# Arduino-DUE-V03-Rocket.net
KiCad netlist of a schematic drawn in EAGLE
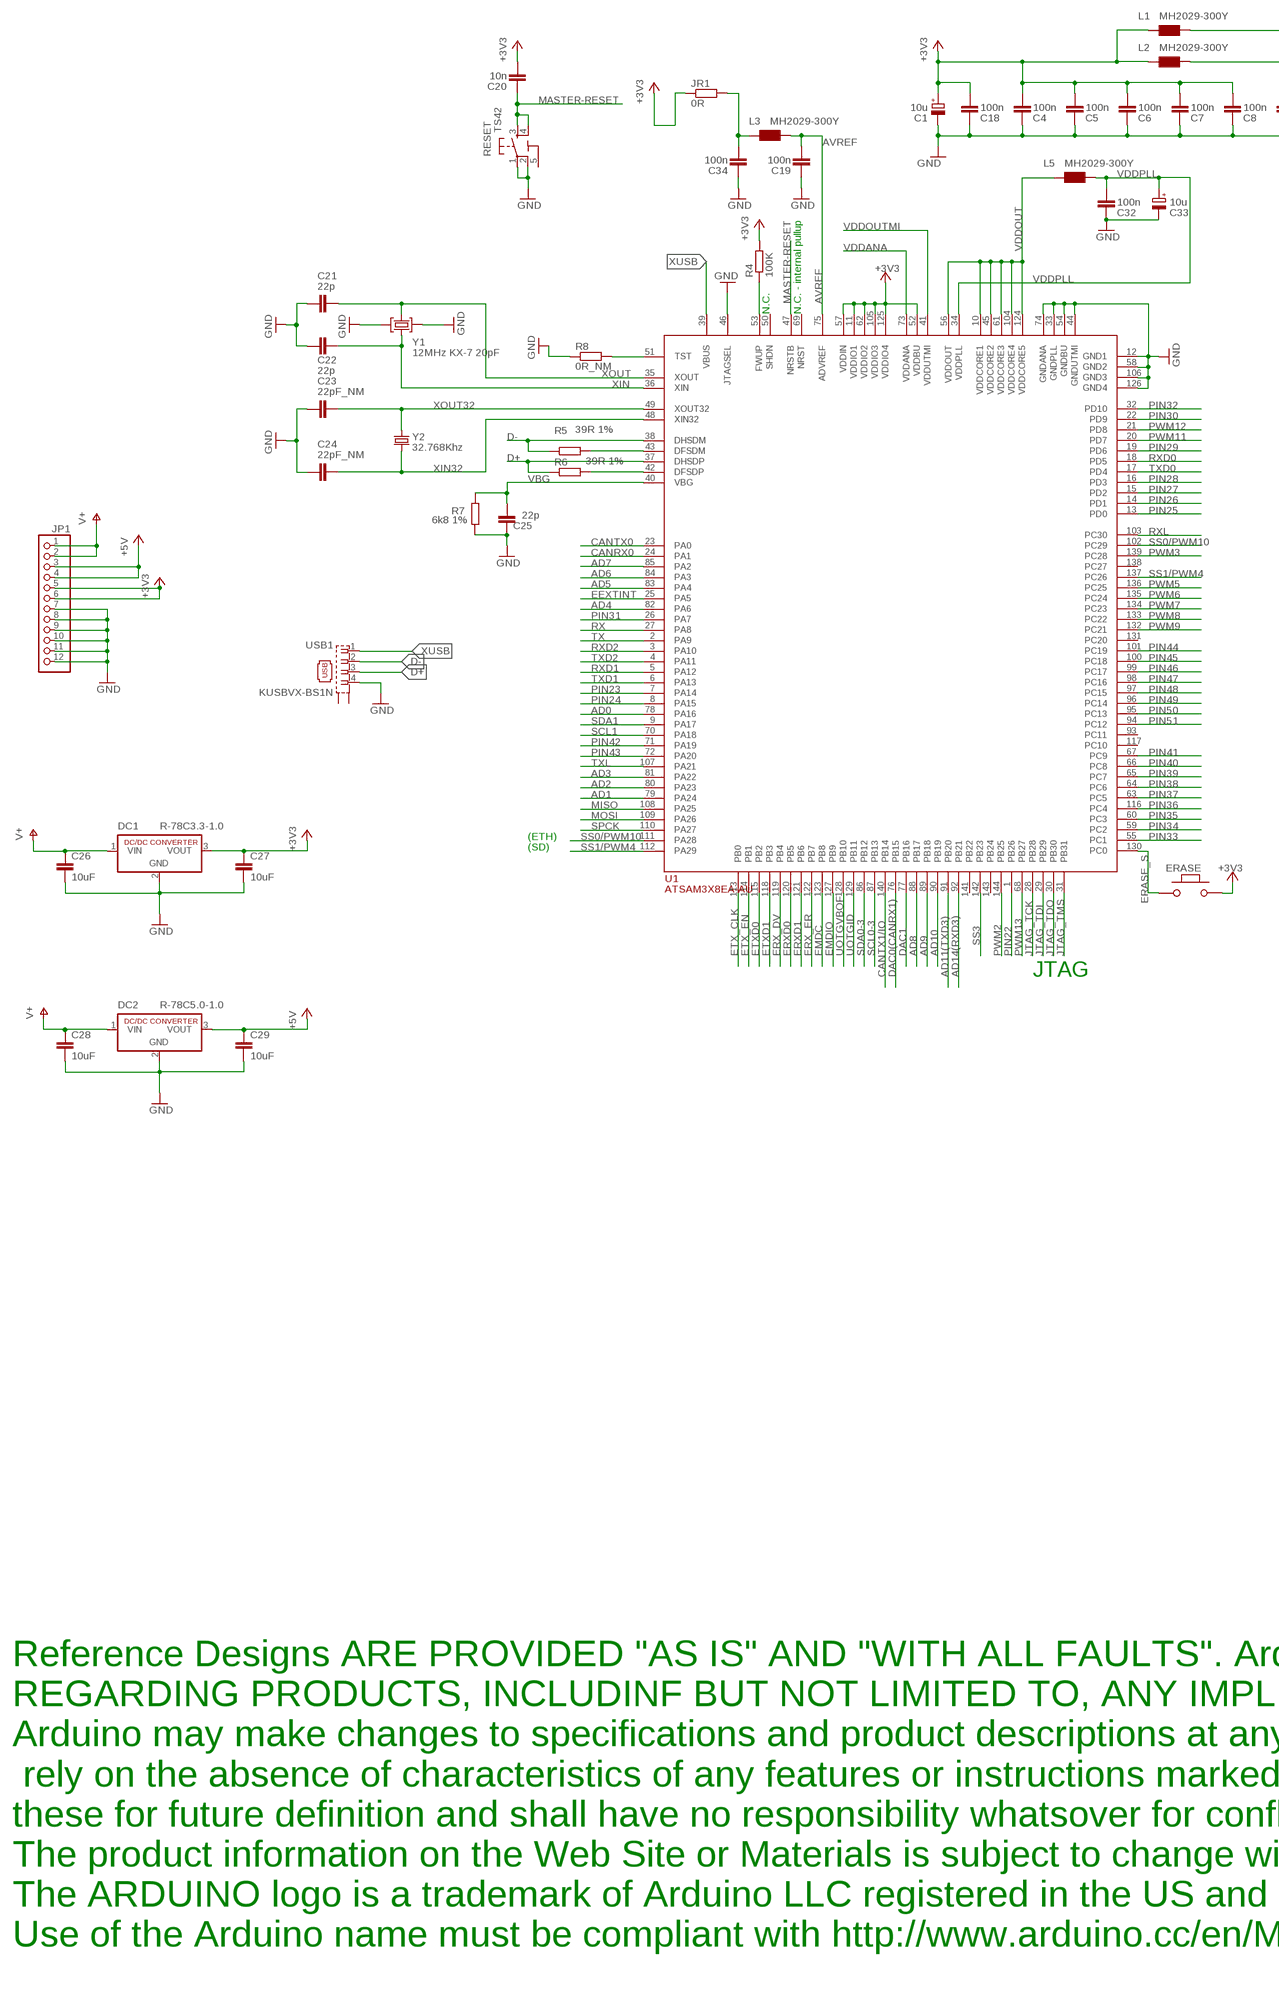
[diagram p0: schematic, sheet 1, part 1 of 2]
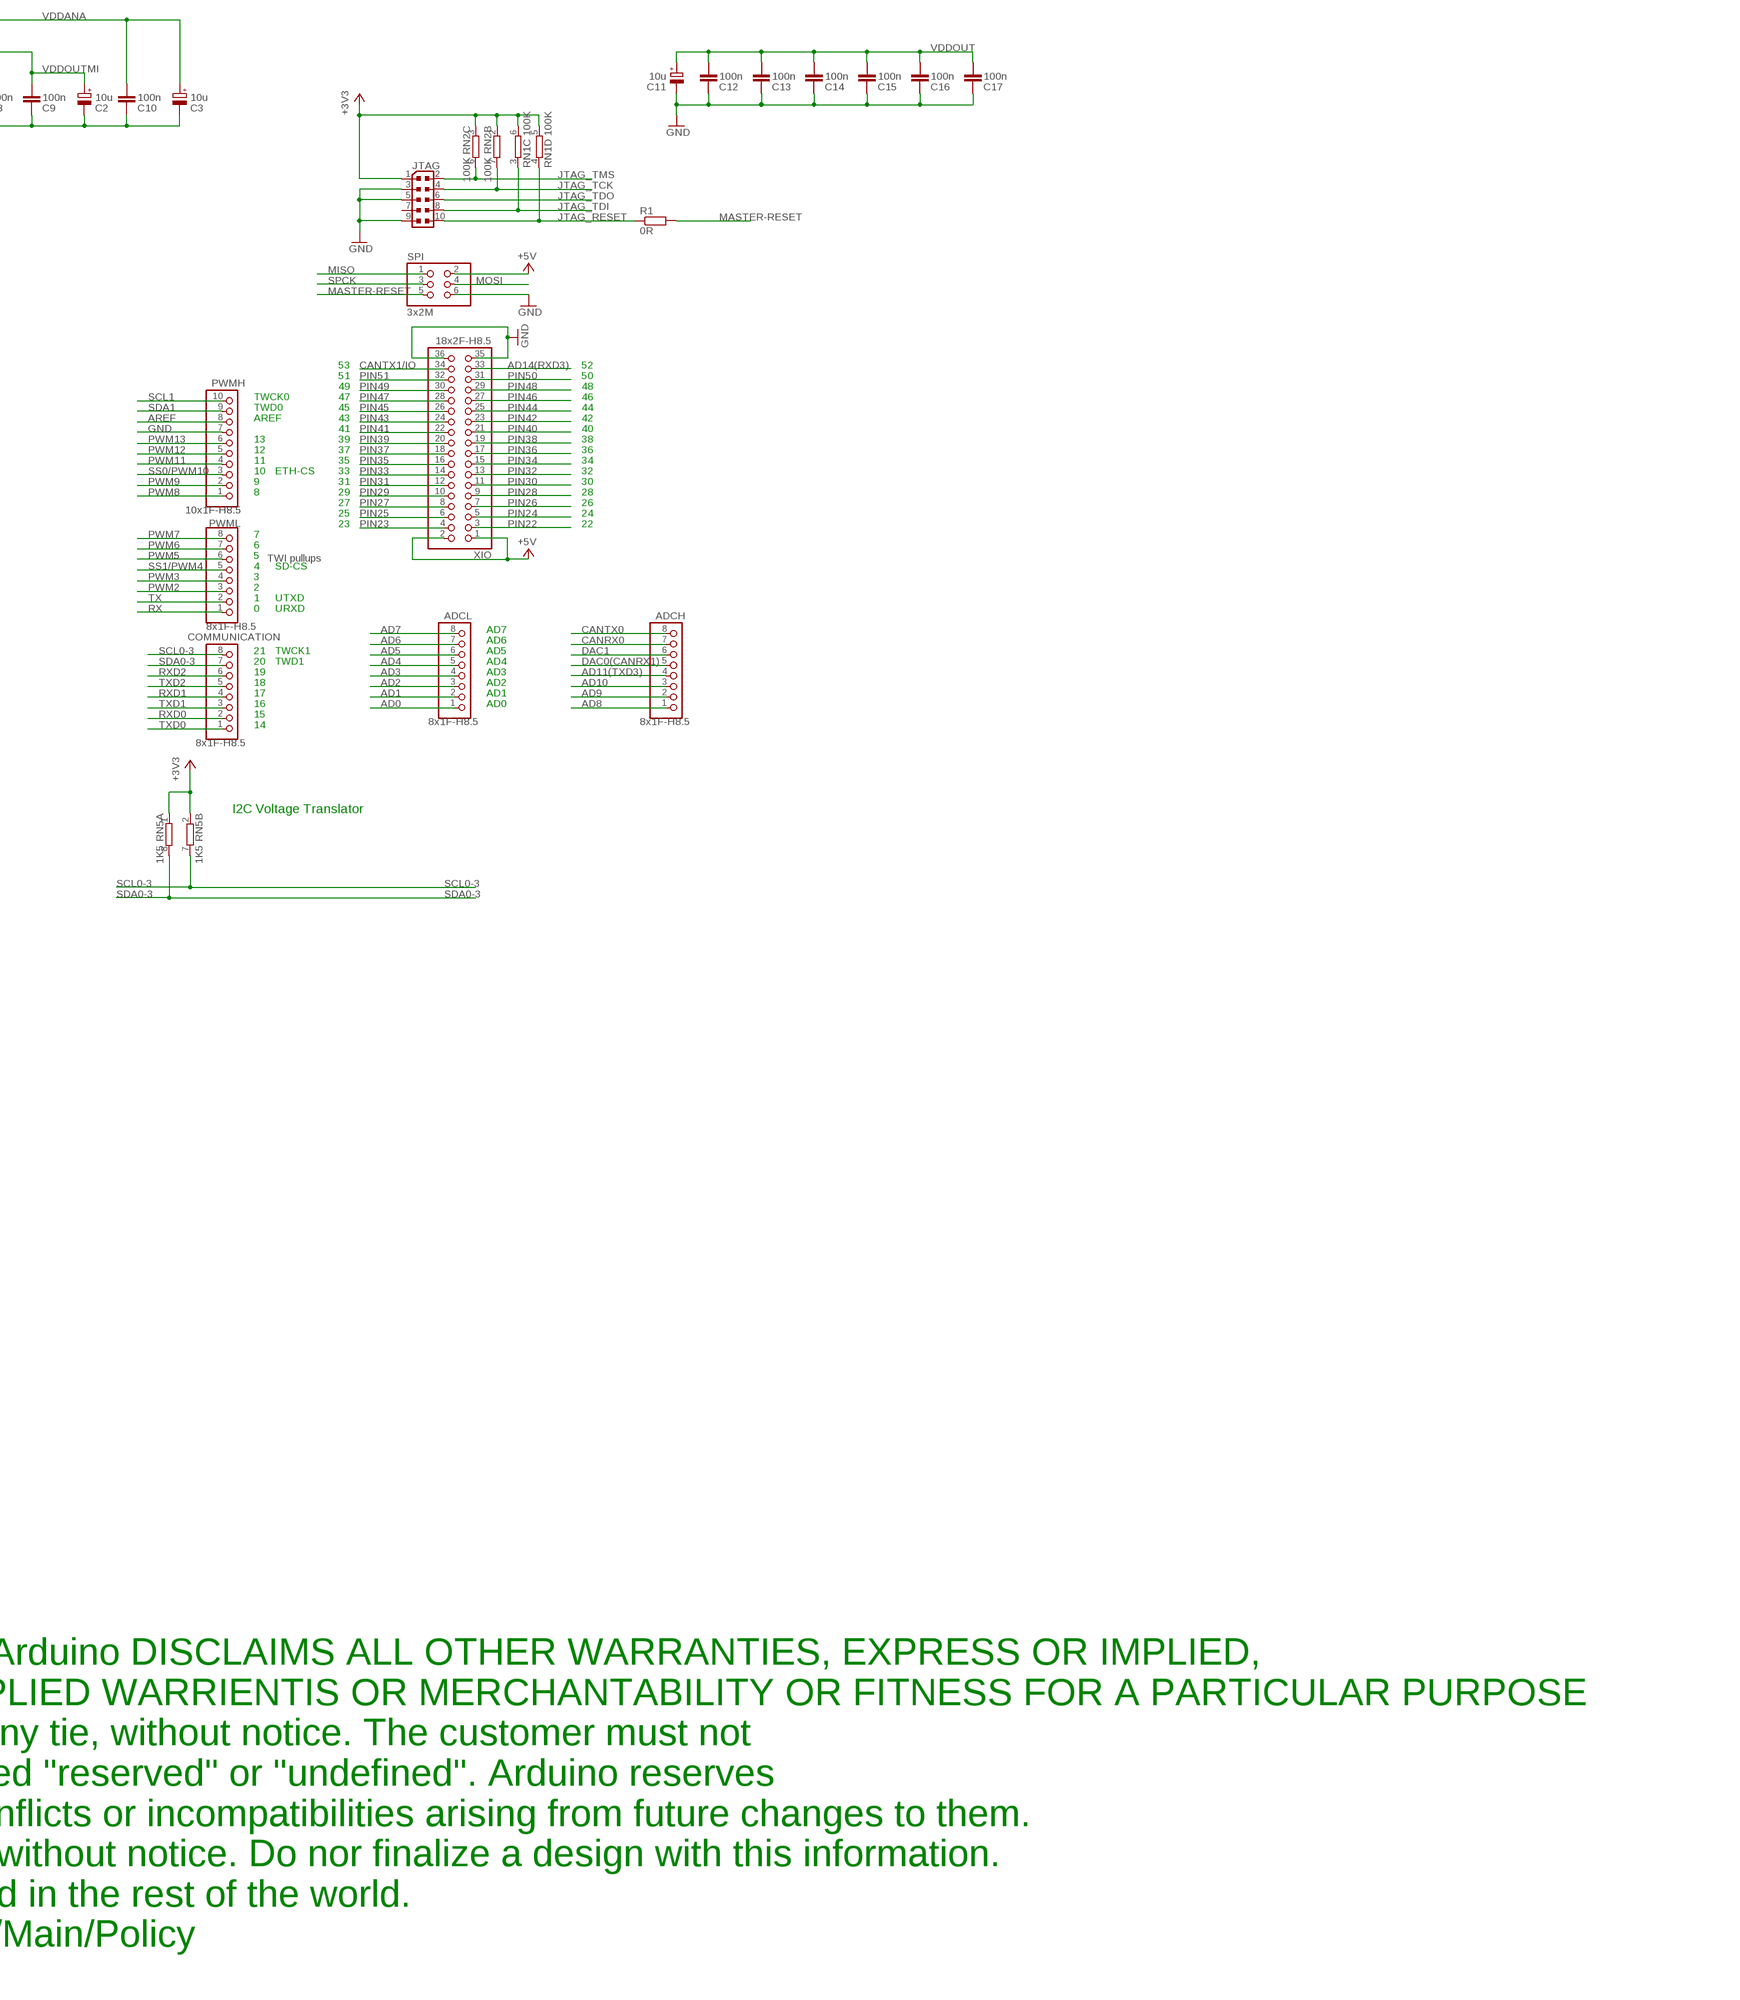
[diagram p1: schematic, sheet 1, part 2 of 2]

(export (version "E")
  (design (tool "Eeschema 10.0.6"))
  (components
    (comp (ref "ADCH")
      (value "8x1F-H8.5")
      (footprint "eagle-import:1X08")
      (libsource (lib "eagle-import") (part "PINHD-1X8"))
    )
    (comp (ref "ADCL")
      (value "8x1F-H8.5")
      (footprint "eagle-import:1X08")
      (libsource (lib "eagle-import") (part "PINHD-1X8"))
    )
    (comp (ref "C1")
      (value "10u")
      (footprint "eagle-import:SMC_B")
      (libsource (lib "eagle-import") (part "CPOL-EUSMCB"))
    )
    (comp (ref "C2")
      (value "10u")
      (footprint "eagle-import:SMC_B")
      (libsource (lib "eagle-import") (part "CPOL-EUSMCB"))
    )
    (comp (ref "C3")
      (value "10u")
      (footprint "eagle-import:SMC_B")
      (libsource (lib "eagle-import") (part "CPOL-EUSMCB"))
    )
    (comp (ref "C4")
      (value "100n")
      (footprint "eagle-import:C0402")
      (libsource (lib "eagle-import") (part "C-EUC0402"))
    )
    (comp (ref "C5")
      (value "100n")
      (footprint "eagle-import:C0402")
      (libsource (lib "eagle-import") (part "C-EUC0402"))
    )
    (comp (ref "C6")
      (value "100n")
      (footprint "eagle-import:C0402")
      (libsource (lib "eagle-import") (part "C-EUC0402"))
    )
    (comp (ref "C7")
      (value "100n")
      (footprint "eagle-import:C0402")
      (libsource (lib "eagle-import") (part "C-EUC0402"))
    )
    (comp (ref "C8")
      (value "100n")
      (footprint "eagle-import:C0402")
      (libsource (lib "eagle-import") (part "C-EUC0402"))
    )
    (comp (ref "C9")
      (value "100n")
      (footprint "eagle-import:C0402")
      (libsource (lib "eagle-import") (part "C-EUC0402"))
    )
    (comp (ref "C10")
      (value "100n")
      (footprint "eagle-import:C0402")
      (libsource (lib "eagle-import") (part "C-EUC0402"))
    )
    (comp (ref "C11")
      (value "10u")
      (footprint "eagle-import:SMC_B")
      (libsource (lib "eagle-import") (part "CPOL-EUSMCB"))
    )
    (comp (ref "C12")
      (value "100n")
      (footprint "eagle-import:C0402")
      (libsource (lib "eagle-import") (part "C-EUC0402"))
    )
    (comp (ref "C13")
      (value "100n")
      (footprint "eagle-import:C0402")
      (libsource (lib "eagle-import") (part "C-EUC0402"))
    )
    (comp (ref "C14")
      (value "100n")
      (footprint "eagle-import:C0402")
      (libsource (lib "eagle-import") (part "C-EUC0402"))
    )
    (comp (ref "C15")
      (value "100n")
      (footprint "eagle-import:C0402")
      (libsource (lib "eagle-import") (part "C-EUC0402"))
    )
    (comp (ref "C16")
      (value "100n")
      (footprint "eagle-import:C0402")
      (libsource (lib "eagle-import") (part "C-EUC0402"))
    )
    (comp (ref "C17")
      (value "100n")
      (footprint "eagle-import:C0402")
      (libsource (lib "eagle-import") (part "C-EUC0402"))
    )
    (comp (ref "C18")
      (value "100n")
      (footprint "eagle-import:C0402")
      (libsource (lib "eagle-import") (part "C-EUC0402"))
    )
    (comp (ref "C19")
      (value "100n")
      (footprint "eagle-import:C0402")
      (libsource (lib "eagle-import") (part "C-EUC0402"))
    )
    (comp (ref "C20")
      (value "10n")
      (footprint "eagle-import:C0402")
      (libsource (lib "eagle-import") (part "C-EUC0402"))
    )
    (comp (ref "C21")
      (value "22p")
      (footprint "eagle-import:C0402")
      (libsource (lib "eagle-import") (part "C-EUC0402"))
    )
    (comp (ref "C22")
      (value "22p")
      (footprint "eagle-import:C0402")
      (libsource (lib "eagle-import") (part "C-EUC0402"))
    )
    (comp (ref "C23")
      (value "22pF_NM")
      (footprint "eagle-import:C0402")
      (libsource (lib "eagle-import") (part "C-EUC0402"))
    )
    (comp (ref "C24")
      (value "22pF_NM")
      (footprint "eagle-import:C0402")
      (libsource (lib "eagle-import") (part "C-EUC0402"))
    )
    (comp (ref "C25")
      (value "22p")
      (footprint "eagle-import:C0402")
      (libsource (lib "eagle-import") (part "C-EUC0402"))
    )
    (comp (ref "C26")
      (value "10uF")
      (footprint "eagle-import:C050-030X075")
      (libsource (lib "eagle-import") (part "resistor_348_C-EU050-030X075"))
    )
    (comp (ref "C27")
      (value "10uF")
      (footprint "eagle-import:C050-030X075")
      (libsource (lib "eagle-import") (part "resistor_348_C-EU050-030X075"))
    )
    (comp (ref "C28")
      (value "10uF")
      (footprint "eagle-import:C050-030X075")
      (libsource (lib "eagle-import") (part "resistor_348_C-EU050-030X075"))
    )
    (comp (ref "C29")
      (value "10uF")
      (footprint "eagle-import:C050-030X075")
      (libsource (lib "eagle-import") (part "resistor_348_C-EU050-030X075"))
    )
    (comp (ref "C32")
      (value "100n")
      (footprint "eagle-import:C0402")
      (libsource (lib "eagle-import") (part "C-EUC0402"))
    )
    (comp (ref "C33")
      (value "10u")
      (footprint "eagle-import:SMC_B")
      (libsource (lib "eagle-import") (part "CPOL-EUSMCB"))
    )
    (comp (ref "C34")
      (value "100n")
      (footprint "eagle-import:C0402")
      (libsource (lib "eagle-import") (part "C-EUC0402"))
    )
    (comp (ref "COMMUNICATION")
      (value "8x1F-H8.5")
      (footprint "eagle-import:1X08")
      (libsource (lib "eagle-import") (part "PINHD-1X8"))
    )
    (comp (ref "DC1")
      (value "R-78C3.3-1.0")
      (footprint "eagle-import:SIP3")
      (libsource (lib "eagle-import") (part "R-78C-1.03.3"))
    )
    (comp (ref "DC2")
      (value "R-78C5.0-1.0")
      (footprint "eagle-import:SIP3")
      (libsource (lib "eagle-import") (part "R-78C-1.05.0"))
    )
    (comp (ref "ERASE")
      (value "MYSMD_PB157")
      (footprint "eagle-import:SMD_157SW")
      (libsource (lib "eagle-import") (part "MYSMD_PB157"))
    )
    (comp (ref "JP1")
      (value "PINHD-1X12")
      (footprint "eagle-import:1X12")
      (libsource (lib "eagle-import") (part "PINHD-1X12"))
    )
    (comp (ref "JR1")
      (value "0R")
      (footprint "eagle-import:R0402")
      (libsource (lib "eagle-import") (part "R-EU_R0402"))
    )
    (comp (ref "JTAG")
      (value "PINHEAD_PINHD-2X5PASSO127")
      (footprint "eagle-import:PINHEAD_2X05_127")
      (libsource (lib "eagle-import") (part "PINHEAD_PINHD-2X5PASSO127"))
    )
    (comp (ref "L1")
      (value "MH2029-300Y")
      (footprint "eagle-import:0805")
      (libsource (lib "eagle-import") (part "WE-CBF_0805"))
    )
    (comp (ref "L2")
      (value "MH2029-300Y")
      (footprint "eagle-import:0805")
      (libsource (lib "eagle-import") (part "WE-CBF_0805"))
    )
    (comp (ref "L3")
      (value "MH2029-300Y")
      (footprint "eagle-import:0805")
      (libsource (lib "eagle-import") (part "WE-CBF_0805"))
    )
    (comp (ref "L5")
      (value "MH2029-300Y")
      (footprint "eagle-import:0805")
      (libsource (lib "eagle-import") (part "WE-CBF_0805"))
    )
    (comp (ref "PWMH")
      (value "10x1F-H8.5")
      (footprint "eagle-import:1X10")
      (libsource (lib "eagle-import") (part "PINHD-1X10"))
    )
    (comp (ref "PWML")
      (value "8x1F-H8.5")
      (footprint "eagle-import:1X08")
      (libsource (lib "eagle-import") (part "PINHD-1X8"))
    )
    (comp (ref "R1")
      (value "0R")
      (footprint "eagle-import:R0402")
      (libsource (lib "eagle-import") (part "R-EU_R0402"))
    )
    (comp (ref "R4")
      (value "100K")
      (footprint "eagle-import:R0402")
      (libsource (lib "eagle-import") (part "R-EU_R0402"))
    )
    (comp (ref "R5")
      (value "39R 1%")
      (footprint "eagle-import:R0402")
      (libsource (lib "eagle-import") (part "R-EU_R0402"))
    )
    (comp (ref "R6")
      (value "39R 1%")
      (footprint "eagle-import:R0402")
      (libsource (lib "eagle-import") (part "R-EU_R0402"))
    )
    (comp (ref "R7")
      (value "6k8 1%")
      (footprint "eagle-import:R0603-ROUND")
      (libsource (lib "eagle-import") (part "R-EU_R0603"))
    )
    (comp (ref "R8")
      (value "0R_NM")
      (footprint "eagle-import:R0402")
      (libsource (lib "eagle-import") (part "R-EU_R0402"))
    )
    (comp (ref "RESET")
      (value "TS42")
      (footprint "eagle-import:TS42")
      (libsource (lib "eagle-import") (part "TS42"))
    )
    (comp (ref "RN1")
      (value "100K")
      (footprint "eagle-import:CAT16")
      (libsource (lib "eagle-import") (part "4R-NCAT16"))
    )
    (comp (ref "RN2")
      (value "100K")
      (footprint "eagle-import:CAT16")
      (libsource (lib "eagle-import") (part "4R-NCAT16"))
    )
    (comp (ref "RN5")
      (value "1K5")
      (footprint "eagle-import:CAT16")
      (libsource (lib "eagle-import") (part "4R-NCAT16"))
    )
    (comp (ref "SPI")
      (value "3x2M")
      (footprint "eagle-import:2X03")
      (libsource (lib "eagle-import") (part "PINHD-2X3"))
    )
    (comp (ref "U1")
      (value "ATSAM3X8EA-AU")
      (footprint "eagle-import:LQFP144")
      (libsource (lib "eagle-import") (part "ATSAM3X/AAU"))
    )
    (comp (ref "USB1")
      (value "KUSBVX-BS1N")
      (footprint "eagle-import:KUSBVX-BS1N")
      (libsource (lib "eagle-import") (part "KUSBVX-BS1N"))
    )
    (comp (ref "XIO")
      (value "18x2F-H8.5")
      (footprint "eagle-import:2X18")
      (libsource (lib "eagle-import") (part "PINHD-2X18"))
    )
    (comp (ref "Y1")
      (value "12MHz KX-7 20pF")
      (footprint "eagle-import:CRYSTAL-3.2-2.5")
      (libsource (lib "eagle-import") (part "CRYSTAL-3.2-2.5"))
    )
    (comp (ref "Y2")
      (value "32.768Khz")
      (footprint "eagle-import:RESONATOR_EPSON_FC_145")
      (libsource (lib "eagle-import") (part "RESONATOR_EPSON_FC_145"))
    )
  )
  (nets
    (net (code "1") (name "+3V3") (class "Default")
      (node (ref "C1") (pin "+") (pinfunction "+_+") (pintype "passive"))
      (node (ref "C18") (pin "2") (pinfunction "2_2") (pintype "passive"))
      (node (ref "C20") (pin "2") (pinfunction "2_2") (pintype "passive"))
      (node (ref "C27") (pin "1") (pinfunction "1_1") (pintype "passive"))
      (node (ref "C4") (pin "2") (pinfunction "2_2") (pintype "passive"))
      (node (ref "C5") (pin "2") (pinfunction "2_2") (pintype "passive"))
      (node (ref "C6") (pin "2") (pinfunction "2_2") (pintype "passive"))
      (node (ref "C7") (pin "2") (pinfunction "2_2") (pintype "passive"))
      (node (ref "C8") (pin "2") (pinfunction "2_2") (pintype "passive"))
      (node (ref "DC1") (pin "3") (pinfunction "VOUT_3") (pintype "passive"))
      (node (ref "ERASE") (pin "1") (pinfunction "1_1") (pintype "passive"))
      (node (ref "JP1") (pin "5") (pinfunction "5_5") (pintype "passive"))
      (node (ref "JP1") (pin "6") (pinfunction "6_6") (pintype "passive"))
      (node (ref "JR1") (pin "1") (pinfunction "1_1") (pintype "passive"))
      (node (ref "JTAG") (pin "1") (pinfunction "1_1") (pintype "passive"))
      (node (ref "L1") (pin "1") (pinfunction "1_1") (pintype "passive"))
      (node (ref "L2") (pin "1") (pinfunction "1_1") (pintype "passive"))
      (node (ref "R4") (pin "2") (pinfunction "2_2") (pintype "passive"))
      (node (ref "RN1") (pin "5") (pinfunction "2_5") (pintype "passive"))
      (node (ref "RN1") (pin "6") (pinfunction "2_6") (pintype "passive"))
      (node (ref "RN2") (pin "2") (pinfunction "1_2") (pintype "passive"))
      (node (ref "RN2") (pin "3") (pinfunction "1_3") (pintype "passive"))
      (node (ref "RN5") (pin "1") (pinfunction "1_1") (pintype "passive"))
      (node (ref "RN5") (pin "2") (pinfunction "1_2") (pintype "passive"))
      (node (ref "U1") (pin "105") (pinfunction "VDDIO3_105") (pintype "power_in"))
      (node (ref "U1") (pin "11") (pinfunction "VDDIO1_11") (pintype "power_in"))
      (node (ref "U1") (pin "125") (pinfunction "VDDIO4_125") (pintype "power_in"))
      (node (ref "U1") (pin "52") (pinfunction "VDDBU_52") (pintype "power_in"))
      (node (ref "U1") (pin "57") (pinfunction "VDDIN_57") (pintype "power_in"))
      (node (ref "U1") (pin "62") (pinfunction "VDDIO2_62") (pintype "power_in"))
    )
    (net (code "2") (name "+5V") (class "Default")
      (node (ref "C29") (pin "1") (pinfunction "1_1") (pintype "passive"))
      (node (ref "DC2") (pin "3") (pinfunction "VOUT_3") (pintype "passive"))
      (node (ref "JP1") (pin "3") (pinfunction "3_3") (pintype "passive"))
      (node (ref "JP1") (pin "4") (pinfunction "4_4") (pintype "passive"))
      (node (ref "SPI") (pin "2") (pinfunction "2_2") (pintype "passive"))
      (node (ref "XIO") (pin "1") (pinfunction "1_1") (pintype "passive"))
      (node (ref "XIO") (pin "2") (pinfunction "2_2") (pintype "passive"))
    )
    (net (code "3") (name "/5-GND") (class "Default")
      (node (ref "RESET") (pin "5") (pinfunction "5-GND_5") (pintype "power_in"))
    )
    (net (code "4") (name "/AD0") (class "Default")
      (node (ref "ADCL") (pin "1") (pinfunction "1_1") (pintype "passive"))
      (node (ref "U1") (pin "78") (pinfunction "PA16_78") (pintype "bidirectional"))
    )
    (net (code "5") (name "/AD1") (class "Default")
      (node (ref "ADCL") (pin "2") (pinfunction "2_2") (pintype "passive"))
      (node (ref "U1") (pin "79") (pinfunction "PA24_79") (pintype "bidirectional"))
    )
    (net (code "6") (name "/AD2") (class "Default")
      (node (ref "ADCL") (pin "3") (pinfunction "3_3") (pintype "passive"))
      (node (ref "U1") (pin "80") (pinfunction "PA23_80") (pintype "bidirectional"))
    )
    (net (code "7") (name "/AD3") (class "Default")
      (node (ref "ADCL") (pin "4") (pinfunction "4_4") (pintype "passive"))
      (node (ref "U1") (pin "81") (pinfunction "PA22_81") (pintype "bidirectional"))
    )
    (net (code "8") (name "/AD4") (class "Default")
      (node (ref "ADCL") (pin "5") (pinfunction "5_5") (pintype "passive"))
      (node (ref "U1") (pin "82") (pinfunction "PA6_82") (pintype "bidirectional"))
    )
    (net (code "9") (name "/AD5") (class "Default")
      (node (ref "ADCL") (pin "6") (pinfunction "6_6") (pintype "passive"))
      (node (ref "U1") (pin "83") (pinfunction "PA4_83") (pintype "bidirectional"))
    )
    (net (code "10") (name "/AD6") (class "Default")
      (node (ref "ADCL") (pin "7") (pinfunction "7_7") (pintype "passive"))
      (node (ref "U1") (pin "84") (pinfunction "PA3_84") (pintype "bidirectional"))
    )
    (net (code "11") (name "/AD7") (class "Default")
      (node (ref "ADCL") (pin "8") (pinfunction "8_8") (pintype "passive"))
      (node (ref "U1") (pin "85") (pinfunction "PA2_85") (pintype "bidirectional"))
    )
    (net (code "12") (name "/AD8") (class "Default")
      (node (ref "ADCH") (pin "1") (pinfunction "1_1") (pintype "passive"))
      (node (ref "U1") (pin "88") (pinfunction "PB17_88") (pintype "bidirectional"))
    )
    (net (code "13") (name "/AD9") (class "Default")
      (node (ref "ADCH") (pin "2") (pinfunction "2_2") (pintype "passive"))
      (node (ref "U1") (pin "89") (pinfunction "PB18_89") (pintype "bidirectional"))
    )
    (net (code "14") (name "/AD10") (class "Default")
      (node (ref "ADCH") (pin "3") (pinfunction "3_3") (pintype "passive"))
      (node (ref "U1") (pin "90") (pinfunction "PB19_90") (pintype "bidirectional"))
    )
    (net (code "15") (name "/AD11(TXD3)") (class "Default")
      (node (ref "ADCH") (pin "4") (pinfunction "4_4") (pintype "passive"))
      (node (ref "U1") (pin "91") (pinfunction "PB20_91") (pintype "bidirectional"))
    )
    (net (code "16") (name "/AD14(RXD3)") (class "Default")
      (node (ref "U1") (pin "92") (pinfunction "PB21_92") (pintype "bidirectional"))
      (node (ref "XIO") (pin "33") (pinfunction "33_33") (pintype "passive"))
    )
    (net (code "17") (name "/AREF") (class "Default")
      (node (ref "PWMH") (pin "8") (pinfunction "8_8") (pintype "passive"))
    )
    (net (code "18") (name "/AVREF") (class "Default")
      (node (ref "C19") (pin "2") (pinfunction "2_2") (pintype "passive"))
      (node (ref "L3") (pin "2") (pinfunction "2_2") (pintype "passive"))
      (node (ref "U1") (pin "75") (pinfunction "ADVREF_75") (pintype "power_in"))
    )
    (net (code "19") (name "/CANRX0") (class "Default")
      (node (ref "ADCH") (pin "7") (pinfunction "7_7") (pintype "passive"))
      (node (ref "U1") (pin "24") (pinfunction "PA1_24") (pintype "bidirectional"))
    )
    (net (code "20") (name "/CANTX0") (class "Default")
      (node (ref "ADCH") (pin "8") (pinfunction "8_8") (pintype "passive"))
      (node (ref "U1") (pin "23") (pinfunction "PA0_23") (pintype "bidirectional"))
    )
    (net (code "21") (name "/CANTX1{slash}IO") (class "Default")
      (node (ref "U1") (pin "140") (pinfunction "PB14_140") (pintype "bidirectional"))
      (node (ref "XIO") (pin "34") (pinfunction "34_34") (pintype "passive"))
    )
    (net (code "22") (name "/DAC0(CANRX1)") (class "Default")
      (node (ref "ADCH") (pin "5") (pinfunction "5_5") (pintype "passive"))
      (node (ref "U1") (pin "76") (pinfunction "PB15_76") (pintype "bidirectional"))
    )
    (net (code "23") (name "/DAC1") (class "Default")
      (node (ref "ADCH") (pin "6") (pinfunction "6_6") (pintype "passive"))
      (node (ref "U1") (pin "77") (pinfunction "PB16_77") (pintype "bidirectional"))
    )
    (net (code "24") (name "/EEXTINT") (class "Default")
      (node (ref "U1") (pin "25") (pinfunction "PA5_25") (pintype "bidirectional"))
    )
    (net (code "25") (name "/EMDC") (class "Default")
      (node (ref "U1") (pin "123") (pinfunction "PB8_123") (pintype "bidirectional"))
    )
    (net (code "26") (name "/EMDIO") (class "Default")
      (node (ref "U1") (pin "127") (pinfunction "PB9_127") (pintype "bidirectional"))
    )
    (net (code "27") (name "/ERASE_S") (class "Default")
      (node (ref "ERASE") (pin "2") (pinfunction "2_2") (pintype "passive"))
      (node (ref "U1") (pin "130") (pinfunction "PC0_130") (pintype "bidirectional"))
    )
    (net (code "28") (name "/ERXD0") (class "Default")
      (node (ref "U1") (pin "120") (pinfunction "PB5_120") (pintype "bidirectional"))
    )
    (net (code "29") (name "/ERXD1") (class "Default")
      (node (ref "U1") (pin "121") (pinfunction "PB6_121") (pintype "bidirectional"))
    )
    (net (code "30") (name "/ERX_DV") (class "Default")
      (node (ref "U1") (pin "119") (pinfunction "PB4_119") (pintype "bidirectional"))
    )
    (net (code "31") (name "/ERX_ER") (class "Default")
      (node (ref "U1") (pin "122") (pinfunction "PB7_122") (pintype "bidirectional"))
    )
    (net (code "32") (name "/ETXD0") (class "Default")
      (node (ref "U1") (pin "115") (pinfunction "PB2_115") (pintype "bidirectional"))
    )
    (net (code "33") (name "/ETXD1") (class "Default")
      (node (ref "U1") (pin "118") (pinfunction "PB3_118") (pintype "bidirectional"))
    )
    (net (code "34") (name "/ETX_CLK") (class "Default")
      (node (ref "U1") (pin "113") (pinfunction "PB0_113") (pintype "bidirectional"))
    )
    (net (code "35") (name "/ETX_EN") (class "Default")
      (node (ref "U1") (pin "114") (pinfunction "PB1_114") (pintype "bidirectional"))
    )
    (net (code "36") (name "/JTAG_RESET") (class "Default")
      (node (ref "JTAG") (pin "10") (pinfunction "10_10") (pintype "passive"))
      (node (ref "R1") (pin "1") (pinfunction "1_1") (pintype "passive"))
      (node (ref "RN1") (pin "4") (pinfunction "1_4") (pintype "passive"))
    )
    (net (code "37") (name "/JTAG_TCK") (class "Default")
      (node (ref "JTAG") (pin "4") (pinfunction "4_4") (pintype "passive"))
      (node (ref "RN2") (pin "7") (pinfunction "2_7") (pintype "passive"))
      (node (ref "U1") (pin "28") (pinfunction "PB28_28") (pintype "bidirectional"))
    )
    (net (code "38") (name "/JTAG_TDI") (class "Default")
      (node (ref "JTAG") (pin "8") (pinfunction "8_8") (pintype "passive"))
      (node (ref "RN1") (pin "3") (pinfunction "1_3") (pintype "passive"))
      (node (ref "U1") (pin "29") (pinfunction "PB29_29") (pintype "bidirectional"))
    )
    (net (code "39") (name "/JTAG_TDO") (class "Default")
      (node (ref "JTAG") (pin "6") (pinfunction "6_6") (pintype "passive"))
      (node (ref "U1") (pin "30") (pinfunction "PB30_30") (pintype "bidirectional"))
    )
    (net (code "40") (name "/JTAG_TMS") (class "Default")
      (node (ref "JTAG") (pin "2") (pinfunction "2_2") (pintype "passive"))
      (node (ref "RN2") (pin "6") (pinfunction "2_6") (pintype "passive"))
      (node (ref "U1") (pin "31") (pinfunction "PB31_31") (pintype "bidirectional"))
    )
    (net (code "41") (name "/MASTER-RESET") (class "Default")
      (node (ref "C20") (pin "1") (pinfunction "1_1") (pintype "passive"))
      (node (ref "R1") (pin "2") (pinfunction "2_2") (pintype "passive"))
      (node (ref "RESET") (pin "3") (pinfunction "3_3") (pintype "passive"))
      (node (ref "RESET") (pin "4") (pinfunction "4_4") (pintype "passive"))
      (node (ref "SPI") (pin "5") (pinfunction "5_5") (pintype "passive"))
      (node (ref "U1") (pin "47") (pinfunction "NRSTB_47") (pintype "input"))
    )
    (net (code "42") (name "/MISO") (class "Default")
      (node (ref "SPI") (pin "1") (pinfunction "1_1") (pintype "passive"))
      (node (ref "U1") (pin "108") (pinfunction "PA25_108") (pintype "bidirectional"))
    )
    (net (code "43") (name "/MOSI") (class "Default")
      (node (ref "SPI") (pin "4") (pinfunction "4_4") (pintype "passive"))
      (node (ref "U1") (pin "109") (pinfunction "PA26_109") (pintype "bidirectional"))
    )
    (net (code "44") (name "/PIN22") (class "Default")
      (node (ref "U1") (pin "1") (pinfunction "PB26_1") (pintype "bidirectional"))
      (node (ref "XIO") (pin "3") (pinfunction "3_3") (pintype "passive"))
    )
    (net (code "45") (name "/PIN23") (class "Default")
      (node (ref "U1") (pin "7") (pinfunction "PA14_7") (pintype "bidirectional"))
      (node (ref "XIO") (pin "4") (pinfunction "4_4") (pintype "passive"))
    )
    (net (code "46") (name "/PIN24") (class "Default")
      (node (ref "U1") (pin "8") (pinfunction "PA15_8") (pintype "bidirectional"))
      (node (ref "XIO") (pin "5") (pinfunction "5_5") (pintype "passive"))
    )
    (net (code "47") (name "/PIN25") (class "Default")
      (node (ref "U1") (pin "13") (pinfunction "PD0_13") (pintype "bidirectional"))
      (node (ref "XIO") (pin "6") (pinfunction "6_6") (pintype "passive"))
    )
    (net (code "48") (name "/PIN26") (class "Default")
      (node (ref "U1") (pin "14") (pinfunction "PD1_14") (pintype "bidirectional"))
      (node (ref "XIO") (pin "7") (pinfunction "7_7") (pintype "passive"))
    )
    (net (code "49") (name "/PIN27") (class "Default")
      (node (ref "U1") (pin "15") (pinfunction "PD2_15") (pintype "bidirectional"))
      (node (ref "XIO") (pin "8") (pinfunction "8_8") (pintype "passive"))
    )
    (net (code "50") (name "/PIN28") (class "Default")
      (node (ref "U1") (pin "16") (pinfunction "PD3_16") (pintype "bidirectional"))
      (node (ref "XIO") (pin "9") (pinfunction "9_9") (pintype "passive"))
    )
    (net (code "51") (name "/PIN29") (class "Default")
      (node (ref "U1") (pin "19") (pinfunction "PD6_19") (pintype "bidirectional"))
      (node (ref "XIO") (pin "10") (pinfunction "10_10") (pintype "passive"))
    )
    (net (code "52") (name "/PIN30") (class "Default")
      (node (ref "U1") (pin "22") (pinfunction "PD9_22") (pintype "bidirectional"))
      (node (ref "XIO") (pin "11") (pinfunction "11_11") (pintype "passive"))
    )
    (net (code "53") (name "/PIN31") (class "Default")
      (node (ref "U1") (pin "26") (pinfunction "PA7_26") (pintype "bidirectional"))
      (node (ref "XIO") (pin "12") (pinfunction "12_12") (pintype "passive"))
    )
    (net (code "54") (name "/PIN32") (class "Default")
      (node (ref "U1") (pin "32") (pinfunction "PD10_32") (pintype "bidirectional"))
      (node (ref "XIO") (pin "13") (pinfunction "13_13") (pintype "passive"))
    )
    (net (code "55") (name "/PIN33") (class "Default")
      (node (ref "U1") (pin "55") (pinfunction "PC1_55") (pintype "bidirectional"))
      (node (ref "XIO") (pin "14") (pinfunction "14_14") (pintype "passive"))
    )
    (net (code "56") (name "/PIN34") (class "Default")
      (node (ref "U1") (pin "59") (pinfunction "PC2_59") (pintype "bidirectional"))
      (node (ref "XIO") (pin "15") (pinfunction "15_15") (pintype "passive"))
    )
    (net (code "57") (name "/PIN35") (class "Default")
      (node (ref "U1") (pin "60") (pinfunction "PC3_60") (pintype "bidirectional"))
      (node (ref "XIO") (pin "16") (pinfunction "16_16") (pintype "passive"))
    )
    (net (code "58") (name "/PIN36") (class "Default")
      (node (ref "U1") (pin "116") (pinfunction "PC4_116") (pintype "bidirectional"))
      (node (ref "XIO") (pin "17") (pinfunction "17_17") (pintype "passive"))
    )
    (net (code "59") (name "/PIN37") (class "Default")
      (node (ref "U1") (pin "63") (pinfunction "PC5_63") (pintype "bidirectional"))
      (node (ref "XIO") (pin "18") (pinfunction "18_18") (pintype "passive"))
    )
    (net (code "60") (name "/PIN38") (class "Default")
      (node (ref "U1") (pin "64") (pinfunction "PC6_64") (pintype "bidirectional"))
      (node (ref "XIO") (pin "19") (pinfunction "19_19") (pintype "passive"))
    )
    (net (code "61") (name "/PIN39") (class "Default")
      (node (ref "U1") (pin "65") (pinfunction "PC7_65") (pintype "bidirectional"))
      (node (ref "XIO") (pin "20") (pinfunction "20_20") (pintype "passive"))
    )
    (net (code "62") (name "/PIN40") (class "Default")
      (node (ref "U1") (pin "66") (pinfunction "PC8_66") (pintype "bidirectional"))
      (node (ref "XIO") (pin "21") (pinfunction "21_21") (pintype "passive"))
    )
    (net (code "63") (name "/PIN41") (class "Default")
      (node (ref "U1") (pin "67") (pinfunction "PC9_67") (pintype "bidirectional"))
      (node (ref "XIO") (pin "22") (pinfunction "22_22") (pintype "passive"))
    )
    (net (code "64") (name "/PIN42") (class "Default")
      (node (ref "U1") (pin "71") (pinfunction "PA19_71") (pintype "bidirectional"))
      (node (ref "XIO") (pin "23") (pinfunction "23_23") (pintype "passive"))
    )
    (net (code "65") (name "/PIN43") (class "Default")
      (node (ref "U1") (pin "72") (pinfunction "PA20_72") (pintype "bidirectional"))
      (node (ref "XIO") (pin "24") (pinfunction "24_24") (pintype "passive"))
    )
    (net (code "66") (name "/PIN44") (class "Default")
      (node (ref "U1") (pin "101") (pinfunction "PC19_101") (pintype "bidirectional"))
      (node (ref "XIO") (pin "25") (pinfunction "25_25") (pintype "passive"))
    )
    (net (code "67") (name "/PIN45") (class "Default")
      (node (ref "U1") (pin "100") (pinfunction "PC18_100") (pintype "bidirectional"))
      (node (ref "XIO") (pin "26") (pinfunction "26_26") (pintype "passive"))
    )
    (net (code "68") (name "/PIN46") (class "Default")
      (node (ref "U1") (pin "99") (pinfunction "PC17_99") (pintype "bidirectional"))
      (node (ref "XIO") (pin "27") (pinfunction "27_27") (pintype "passive"))
    )
    (net (code "69") (name "/PIN47") (class "Default")
      (node (ref "U1") (pin "98") (pinfunction "PC16_98") (pintype "bidirectional"))
      (node (ref "XIO") (pin "28") (pinfunction "28_28") (pintype "passive"))
    )
    (net (code "70") (name "/PIN48") (class "Default")
      (node (ref "U1") (pin "97") (pinfunction "PC15_97") (pintype "bidirectional"))
      (node (ref "XIO") (pin "29") (pinfunction "29_29") (pintype "passive"))
    )
    (net (code "71") (name "/PIN49") (class "Default")
      (node (ref "U1") (pin "96") (pinfunction "PC14_96") (pintype "bidirectional"))
      (node (ref "XIO") (pin "30") (pinfunction "30_30") (pintype "passive"))
    )
    (net (code "72") (name "/PIN50") (class "Default")
      (node (ref "U1") (pin "95") (pinfunction "PC13_95") (pintype "bidirectional"))
      (node (ref "XIO") (pin "31") (pinfunction "31_31") (pintype "passive"))
    )
    (net (code "73") (name "/PIN51") (class "Default")
      (node (ref "U1") (pin "94") (pinfunction "PC12_94") (pintype "bidirectional"))
      (node (ref "XIO") (pin "32") (pinfunction "32_32") (pintype "passive"))
    )
    (net (code "74") (name "/PWM2") (class "Default")
      (node (ref "PWML") (pin "3") (pinfunction "3_3") (pintype "passive"))
      (node (ref "U1") (pin "144") (pinfunction "PB25_144") (pintype "bidirectional"))
    )
    (net (code "75") (name "/PWM3") (class "Default")
      (node (ref "PWML") (pin "4") (pinfunction "4_4") (pintype "passive"))
      (node (ref "U1") (pin "139") (pinfunction "PC28_139") (pintype "bidirectional"))
    )
    (net (code "76") (name "/PWM5") (class "Default")
      (node (ref "PWML") (pin "6") (pinfunction "6_6") (pintype "passive"))
      (node (ref "U1") (pin "136") (pinfunction "PC25_136") (pintype "bidirectional"))
    )
    (net (code "77") (name "/PWM6") (class "Default")
      (node (ref "PWML") (pin "7") (pinfunction "7_7") (pintype "passive"))
      (node (ref "U1") (pin "135") (pinfunction "PC24_135") (pintype "bidirectional"))
    )
    (net (code "78") (name "/PWM7") (class "Default")
      (node (ref "PWML") (pin "8") (pinfunction "8_8") (pintype "passive"))
      (node (ref "U1") (pin "134") (pinfunction "PC23_134") (pintype "bidirectional"))
    )
    (net (code "79") (name "/PWM8") (class "Default")
      (node (ref "PWMH") (pin "1") (pinfunction "1_1") (pintype "passive"))
      (node (ref "U1") (pin "133") (pinfunction "PC22_133") (pintype "bidirectional"))
    )
    (net (code "80") (name "/PWM9") (class "Default")
      (node (ref "PWMH") (pin "2") (pinfunction "2_2") (pintype "passive"))
      (node (ref "U1") (pin "132") (pinfunction "PC21_132") (pintype "bidirectional"))
    )
    (net (code "81") (name "/PWM11") (class "Default")
      (node (ref "PWMH") (pin "4") (pinfunction "4_4") (pintype "passive"))
      (node (ref "U1") (pin "20") (pinfunction "PD7_20") (pintype "bidirectional"))
    )
    (net (code "82") (name "/PWM12") (class "Default")
      (node (ref "PWMH") (pin "5") (pinfunction "5_5") (pintype "passive"))
      (node (ref "U1") (pin "21") (pinfunction "PD8_21") (pintype "bidirectional"))
    )
    (net (code "83") (name "/PWM13") (class "Default")
      (node (ref "PWMH") (pin "6") (pinfunction "6_6") (pintype "passive"))
      (node (ref "U1") (pin "68") (pinfunction "PB27_68") (pintype "bidirectional"))
    )
    (net (code "84") (name "/RX") (class "Default")
      (node (ref "PWML") (pin "1") (pinfunction "1_1") (pintype "passive"))
      (node (ref "U1") (pin "27") (pinfunction "PA8_27") (pintype "bidirectional"))
    )
    (net (code "85") (name "/RXD0") (class "Default")
      (node (ref "COMMUNICATION") (pin "2") (pinfunction "2_2") (pintype "passive"))
      (node (ref "U1") (pin "18") (pinfunction "PD5_18") (pintype "bidirectional"))
    )
    (net (code "86") (name "/RXD1") (class "Default")
      (node (ref "COMMUNICATION") (pin "4") (pinfunction "4_4") (pintype "passive"))
      (node (ref "U1") (pin "5") (pinfunction "PA12_5") (pintype "bidirectional"))
    )
    (net (code "87") (name "/RXD2") (class "Default")
      (node (ref "COMMUNICATION") (pin "6") (pinfunction "6_6") (pintype "passive"))
      (node (ref "U1") (pin "3") (pinfunction "PA10_3") (pintype "bidirectional"))
    )
    (net (code "88") (name "/RXL") (class "Default")
      (node (ref "U1") (pin "103") (pinfunction "PC30_103") (pintype "bidirectional"))
    )
    (net (code "89") (name "/SCL0-3") (class "Default")
      (node (ref "COMMUNICATION") (pin "8") (pinfunction "8_8") (pintype "passive"))
      (node (ref "RN5") (pin "7") (pinfunction "2_7") (pintype "passive"))
      (node (ref "U1") (pin "87") (pinfunction "PB13_87") (pintype "bidirectional"))
    )
    (net (code "90") (name "/SCL1") (class "Default")
      (node (ref "PWMH") (pin "10") (pinfunction "10_10") (pintype "passive"))
      (node (ref "U1") (pin "70") (pinfunction "PA18_70") (pintype "bidirectional"))
    )
    (net (code "91") (name "/SDA0-3") (class "Default")
      (node (ref "COMMUNICATION") (pin "7") (pinfunction "7_7") (pintype "passive"))
      (node (ref "RN5") (pin "8") (pinfunction "2_8") (pintype "passive"))
      (node (ref "U1") (pin "86") (pinfunction "PB12_86") (pintype "bidirectional"))
    )
    (net (code "92") (name "/SDA1") (class "Default")
      (node (ref "PWMH") (pin "9") (pinfunction "9_9") (pintype "passive"))
      (node (ref "U1") (pin "9") (pinfunction "PA17_9") (pintype "bidirectional"))
    )
    (net (code "93") (name "/SPCK") (class "Default")
      (node (ref "SPI") (pin "3") (pinfunction "3_3") (pintype "passive"))
      (node (ref "U1") (pin "110") (pinfunction "PA27_110") (pintype "bidirectional"))
    )
    (net (code "94") (name "/SS0{slash}PWM10") (class "Default")
      (node (ref "PWMH") (pin "3") (pinfunction "3_3") (pintype "passive"))
      (node (ref "U1") (pin "102") (pinfunction "PC29_102") (pintype "bidirectional"))
      (node (ref "U1") (pin "111") (pinfunction "PA28_111") (pintype "bidirectional"))
    )
    (net (code "95") (name "/SS1{slash}PWM4") (class "Default")
      (node (ref "PWML") (pin "5") (pinfunction "5_5") (pintype "passive"))
      (node (ref "U1") (pin "112") (pinfunction "PA29_112") (pintype "bidirectional"))
      (node (ref "U1") (pin "137") (pinfunction "PC26_137") (pintype "bidirectional"))
    )
    (net (code "96") (name "/SS3") (class "Default")
      (node (ref "U1") (pin "142") (pinfunction "PB23_142") (pintype "bidirectional"))
    )
    (net (code "97") (name "/TX") (class "Default")
      (node (ref "PWML") (pin "2") (pinfunction "2_2") (pintype "passive"))
      (node (ref "U1") (pin "2") (pinfunction "PA9_2") (pintype "bidirectional"))
    )
    (net (code "98") (name "/TXD0") (class "Default")
      (node (ref "COMMUNICATION") (pin "1") (pinfunction "1_1") (pintype "passive"))
      (node (ref "U1") (pin "17") (pinfunction "PD4_17") (pintype "bidirectional"))
    )
    (net (code "99") (name "/TXD1") (class "Default")
      (node (ref "COMMUNICATION") (pin "3") (pinfunction "3_3") (pintype "passive"))
      (node (ref "U1") (pin "6") (pinfunction "PA13_6") (pintype "bidirectional"))
    )
    (net (code "100") (name "/TXD2") (class "Default")
      (node (ref "COMMUNICATION") (pin "5") (pinfunction "5_5") (pintype "passive"))
      (node (ref "U1") (pin "4") (pinfunction "PA11_4") (pintype "bidirectional"))
    )
    (net (code "101") (name "/TXL") (class "Default")
      (node (ref "U1") (pin "107") (pinfunction "PA21_107") (pintype "bidirectional"))
    )
    (net (code "102") (name "/UOTGID") (class "Default")
      (node (ref "U1") (pin "129") (pinfunction "PB11_129") (pintype "bidirectional"))
    )
    (net (code "103") (name "/UOTGVBOF") (class "Default")
      (node (ref "U1") (pin "128") (pinfunction "PB10_128") (pintype "bidirectional"))
    )
    (net (code "104") (name "/VBG") (class "Default")
      (node (ref "C25") (pin "1") (pinfunction "1_1") (pintype "passive"))
      (node (ref "R7") (pin "2") (pinfunction "2_2") (pintype "passive"))
      (node (ref "U1") (pin "40") (pinfunction "VBG_40") (pintype "passive"))
    )
    (net (code "105") (name "/VDDANA") (class "Default")
      (node (ref "C10") (pin "2") (pinfunction "2_2") (pintype "passive"))
      (node (ref "C3") (pin "+") (pinfunction "+_+") (pintype "passive"))
      (node (ref "L1") (pin "2") (pinfunction "2_2") (pintype "passive"))
      (node (ref "U1") (pin "73") (pinfunction "VDDANA_73") (pintype "power_in"))
    )
    (net (code "106") (name "/VDDOUT") (class "Default")
      (node (ref "C11") (pin "+") (pinfunction "+_+") (pintype "passive"))
      (node (ref "C12") (pin "2") (pinfunction "2_2") (pintype "passive"))
      (node (ref "C13") (pin "2") (pinfunction "2_2") (pintype "passive"))
      (node (ref "C14") (pin "2") (pinfunction "2_2") (pintype "passive"))
      (node (ref "C15") (pin "2") (pinfunction "2_2") (pintype "passive"))
      (node (ref "C16") (pin "2") (pinfunction "2_2") (pintype "passive"))
      (node (ref "C17") (pin "2") (pinfunction "2_2") (pintype "passive"))
      (node (ref "L5") (pin "1") (pinfunction "1_1") (pintype "passive"))
      (node (ref "U1") (pin "10") (pinfunction "VDDCORE1_10") (pintype "input"))
      (node (ref "U1") (pin "104") (pinfunction "VDDCORE4_104") (pintype "input"))
      (node (ref "U1") (pin "124") (pinfunction "VDDCORE5_124") (pintype "input"))
      (node (ref "U1") (pin "45") (pinfunction "VDDCORE2_45") (pintype "input"))
      (node (ref "U1") (pin "56") (pinfunction "VDDOUT_56") (pintype "output"))
      (node (ref "U1") (pin "61") (pinfunction "VDDCORE3_61") (pintype "input"))
    )
    (net (code "107") (name "/VDDOUTMI") (class "Default")
      (node (ref "C2") (pin "+") (pinfunction "+_+") (pintype "passive"))
      (node (ref "C9") (pin "2") (pinfunction "2_2") (pintype "passive"))
      (node (ref "L2") (pin "2") (pinfunction "2_2") (pintype "passive"))
      (node (ref "U1") (pin "41") (pinfunction "VDDUTMI_41") (pintype "input"))
    )
    (net (code "108") (name "/VDDPLL") (class "Default")
      (node (ref "C32") (pin "2") (pinfunction "2_2") (pintype "passive"))
      (node (ref "C33") (pin "+") (pinfunction "+_+") (pintype "passive"))
      (node (ref "L5") (pin "2") (pinfunction "2_2") (pintype "passive"))
      (node (ref "U1") (pin "34") (pinfunction "VDDPLL_34") (pintype "input"))
    )
    (net (code "109") (name "/XIN") (class "Default")
      (node (ref "C22") (pin "1") (pinfunction "1_1") (pintype "passive"))
      (node (ref "U1") (pin "36") (pinfunction "XIN_36") (pintype "input"))
      (node (ref "Y1") (pin "1") (pinfunction "C1_1") (pintype "passive"))
    )
    (net (code "110") (name "/XIN32") (class "Default")
      (node (ref "C24") (pin "1") (pinfunction "1_1") (pintype "passive"))
      (node (ref "U1") (pin "48") (pinfunction "XIN32_48") (pintype "output"))
      (node (ref "Y2") (pin "P$2") (pinfunction "2_P$2") (pintype "bidirectional"))
    )
    (net (code "111") (name "/XOUT") (class "Default")
      (node (ref "C21") (pin "1") (pinfunction "1_1") (pintype "passive"))
      (node (ref "U1") (pin "35") (pinfunction "XOUT_35") (pintype "output"))
      (node (ref "Y1") (pin "3") (pinfunction "C2_3") (pintype "passive"))
    )
    (net (code "112") (name "/XOUT32") (class "Default")
      (node (ref "C23") (pin "1") (pinfunction "1_1") (pintype "passive"))
      (node (ref "U1") (pin "49") (pinfunction "XOUT32_49") (pintype "output"))
      (node (ref "Y2") (pin "P$1") (pinfunction "1_P$1") (pintype "bidirectional"))
    )
    (net (code "113") (name "D+") (class "Default")
      (node (ref "R6") (pin "1") (pinfunction "1_1") (pintype "passive"))
      (node (ref "U1") (pin "37") (pinfunction "DHSDP_37") (pintype "bidirectional"))
      (node (ref "USB1") (pin "3") (pinfunction "3_3") (pintype "passive"))
    )
    (net (code "114") (name "D-") (class "Default")
      (node (ref "R5") (pin "1") (pinfunction "1_1") (pintype "passive"))
      (node (ref "U1") (pin "38") (pinfunction "DHSDM_38") (pintype "bidirectional"))
      (node (ref "USB1") (pin "2") (pinfunction "2_2") (pintype "passive"))
    )
    (net (code "115") (name "GND") (class "Default")
      (node (ref "C1") (pin "-") (pinfunction "-_-") (pintype "passive"))
      (node (ref "C10") (pin "1") (pinfunction "1_1") (pintype "passive"))
      (node (ref "C11") (pin "-") (pinfunction "-_-") (pintype "passive"))
      (node (ref "C12") (pin "1") (pinfunction "1_1") (pintype "passive"))
      (node (ref "C13") (pin "1") (pinfunction "1_1") (pintype "passive"))
      (node (ref "C14") (pin "1") (pinfunction "1_1") (pintype "passive"))
      (node (ref "C15") (pin "1") (pinfunction "1_1") (pintype "passive"))
      (node (ref "C16") (pin "1") (pinfunction "1_1") (pintype "passive"))
      (node (ref "C17") (pin "1") (pinfunction "1_1") (pintype "passive"))
      (node (ref "C18") (pin "1") (pinfunction "1_1") (pintype "passive"))
      (node (ref "C19") (pin "1") (pinfunction "1_1") (pintype "passive"))
      (node (ref "C2") (pin "-") (pinfunction "-_-") (pintype "passive"))
      (node (ref "C21") (pin "2") (pinfunction "2_2") (pintype "passive"))
      (node (ref "C22") (pin "2") (pinfunction "2_2") (pintype "passive"))
      (node (ref "C23") (pin "2") (pinfunction "2_2") (pintype "passive"))
      (node (ref "C24") (pin "2") (pinfunction "2_2") (pintype "passive"))
      (node (ref "C25") (pin "2") (pinfunction "2_2") (pintype "passive"))
      (node (ref "C26") (pin "2") (pinfunction "2_2") (pintype "passive"))
      (node (ref "C27") (pin "2") (pinfunction "2_2") (pintype "passive"))
      (node (ref "C28") (pin "2") (pinfunction "2_2") (pintype "passive"))
      (node (ref "C29") (pin "2") (pinfunction "2_2") (pintype "passive"))
      (node (ref "C3") (pin "-") (pinfunction "-_-") (pintype "passive"))
      (node (ref "C32") (pin "1") (pinfunction "1_1") (pintype "passive"))
      (node (ref "C33") (pin "-") (pinfunction "-_-") (pintype "passive"))
      (node (ref "C34") (pin "1") (pinfunction "1_1") (pintype "passive"))
      (node (ref "C4") (pin "1") (pinfunction "1_1") (pintype "passive"))
      (node (ref "C5") (pin "1") (pinfunction "1_1") (pintype "passive"))
      (node (ref "C6") (pin "1") (pinfunction "1_1") (pintype "passive"))
      (node (ref "C7") (pin "1") (pinfunction "1_1") (pintype "passive"))
      (node (ref "C8") (pin "1") (pinfunction "1_1") (pintype "passive"))
      (node (ref "C9") (pin "1") (pinfunction "1_1") (pintype "passive"))
      (node (ref "DC1") (pin "2") (pinfunction "GND_2") (pintype "passive"))
      (node (ref "DC2") (pin "2") (pinfunction "GND_2") (pintype "passive"))
      (node (ref "JP1") (pin "10") (pinfunction "10_10") (pintype "passive"))
      (node (ref "JP1") (pin "11") (pinfunction "11_11") (pintype "passive"))
      (node (ref "JP1") (pin "12") (pinfunction "12_12") (pintype "passive"))
      (node (ref "JP1") (pin "7") (pinfunction "7_7") (pintype "passive"))
      (node (ref "JP1") (pin "8") (pinfunction "8_8") (pintype "passive"))
      (node (ref "JP1") (pin "9") (pinfunction "9_9") (pintype "passive"))
      (node (ref "JTAG") (pin "3") (pinfunction "3_3") (pintype "passive"))
      (node (ref "JTAG") (pin "5") (pinfunction "5_5") (pintype "passive"))
      (node (ref "JTAG") (pin "9") (pinfunction "9_9") (pintype "passive"))
      (node (ref "PWMH") (pin "7") (pinfunction "7_7") (pintype "passive"))
      (node (ref "R7") (pin "1") (pinfunction "1_1") (pintype "passive"))
      (node (ref "R8") (pin "1") (pinfunction "1_1") (pintype "passive"))
      (node (ref "RESET") (pin "1") (pinfunction "1_1") (pintype "passive"))
      (node (ref "RESET") (pin "2") (pinfunction "2_2") (pintype "passive"))
      (node (ref "SPI") (pin "6") (pinfunction "6_6") (pintype "passive"))
      (node (ref "U1") (pin "106") (pinfunction "GND3_106") (pintype "power_in"))
      (node (ref "U1") (pin "12") (pinfunction "GND1_12") (pintype "power_in"))
      (node (ref "U1") (pin "126") (pinfunction "GND4_126") (pintype "power_in"))
      (node (ref "U1") (pin "33") (pinfunction "GNDPLL_33") (pintype "power_in"))
      (node (ref "U1") (pin "44") (pinfunction "GNDUTMI_44") (pintype "power_in"))
      (node (ref "U1") (pin "46") (pinfunction "JTAGSEL_46") (pintype "input"))
      (node (ref "U1") (pin "54") (pinfunction "GNDBU_54") (pintype "power_in"))
      (node (ref "U1") (pin "58") (pinfunction "GND2_58") (pintype "power_in"))
      (node (ref "U1") (pin "74") (pinfunction "GNDANA_74") (pintype "power_in"))
      (node (ref "USB1") (pin "4") (pinfunction "4_4") (pintype "passive"))
      (node (ref "XIO") (pin "35") (pinfunction "35_35") (pintype "passive"))
      (node (ref "XIO") (pin "36") (pinfunction "36_36") (pintype "passive"))
      (node (ref "Y1") (pin "2") (pinfunction "GND_2") (pintype "passive"))
      (node (ref "Y1") (pin "4") (pinfunction "GND_4") (pintype "passive"))
    )
    (net (code "116") (name "Net-(C34-Pad2)") (class "Default")
      (node (ref "C34") (pin "2") (pinfunction "2_2") (pintype "passive"))
      (node (ref "JR1") (pin "2") (pinfunction "2_2") (pintype "passive"))
      (node (ref "L3") (pin "1") (pinfunction "1_1") (pintype "passive"))
    )
    (net (code "117") (name "Net-(U1-DFSDM)") (class "Default")
      (node (ref "R5") (pin "2") (pinfunction "2_2") (pintype "passive"))
      (node (ref "U1") (pin "43") (pinfunction "DFSDM_43") (pintype "input"))
    )
    (net (code "118") (name "Net-(U1-DFSDP)") (class "Default")
      (node (ref "R6") (pin "2") (pinfunction "2_2") (pintype "passive"))
      (node (ref "U1") (pin "42") (pinfunction "DFSDP_42") (pintype "input"))
    )
    (net (code "119") (name "Net-(U1-FWUP)") (class "Default")
      (node (ref "R4") (pin "1") (pinfunction "1_1") (pintype "passive"))
      (node (ref "U1") (pin "53") (pinfunction "FWUP_53") (pintype "input"))
    )
    (net (code "120") (name "Net-(U1-TST)") (class "Default")
      (node (ref "R8") (pin "2") (pinfunction "2_2") (pintype "passive"))
      (node (ref "U1") (pin "51") (pinfunction "TST_51") (pintype "input"))
    )
    (net (code "121") (name "V+") (class "Default")
      (node (ref "C26") (pin "1") (pinfunction "1_1") (pintype "passive"))
      (node (ref "C28") (pin "1") (pinfunction "1_1") (pintype "passive"))
      (node (ref "DC1") (pin "1") (pinfunction "VIN_1") (pintype "passive"))
      (node (ref "DC2") (pin "1") (pinfunction "VIN_1") (pintype "passive"))
      (node (ref "JP1") (pin "1") (pinfunction "1_1") (pintype "passive"))
      (node (ref "JP1") (pin "2") (pinfunction "2_2") (pintype "passive"))
    )
    (net (code "122") (name "XUSB") (class "Default")
      (node (ref "U1") (pin "39") (pinfunction "VBUS_39") (pintype "power_in"))
      (node (ref "USB1") (pin "1") (pinfunction "1_1") (pintype "passive"))
    )
    (net (code "123") (name "unconnected-(JTAG-Pad7)") (class "Default")
      (node (ref "JTAG") (pin "7") (pinfunction "7_7") (pintype "passive"))
    )
    (net (code "124") (name "unconnected-(U1-NRST-Pad69)") (class "Default")
      (node (ref "U1") (pin "69") (pinfunction "NRST_69") (pintype "bidirectional"))
    )
    (net (code "125") (name "unconnected-(U1-PB22-Pad141)") (class "Default")
      (node (ref "U1") (pin "141") (pinfunction "PB22_141") (pintype "bidirectional"))
    )
    (net (code "126") (name "unconnected-(U1-PB24-Pad143)") (class "Default")
      (node (ref "U1") (pin "143") (pinfunction "PB24_143") (pintype "bidirectional"))
    )
    (net (code "127") (name "unconnected-(U1-PC10-Pad117)") (class "Default")
      (node (ref "U1") (pin "117") (pinfunction "PC10_117") (pintype "bidirectional"))
    )
    (net (code "128") (name "unconnected-(U1-PC11-Pad93)") (class "Default")
      (node (ref "U1") (pin "93") (pinfunction "PC11_93") (pintype "bidirectional"))
    )
    (net (code "129") (name "unconnected-(U1-PC20-Pad131)") (class "Default")
      (node (ref "U1") (pin "131") (pinfunction "PC20_131") (pintype "bidirectional"))
    )
    (net (code "130") (name "unconnected-(U1-PC27-Pad138)") (class "Default")
      (node (ref "U1") (pin "138") (pinfunction "PC27_138") (pintype "bidirectional"))
    )
    (net (code "131") (name "unconnected-(U1-SHDN-Pad50)") (class "Default")
      (node (ref "U1") (pin "50") (pinfunction "SHDN_50") (pintype "output"))
    )
    (net (code "132") (name "unconnected-(USB1-S1-PadM1)") (class "Default")
      (node (ref "USB1") (pin "M1") (pinfunction "S1_M1") (pintype "passive"))
    )
    (net (code "133") (name "unconnected-(USB1-S2-PadM2)") (class "Default")
      (node (ref "USB1") (pin "M2") (pinfunction "S2_M2") (pintype "passive"))
    )
  )
)
